# PiBladeBackPlane-V1.net
KiCad netlist of a schematic drawn in EAGLE
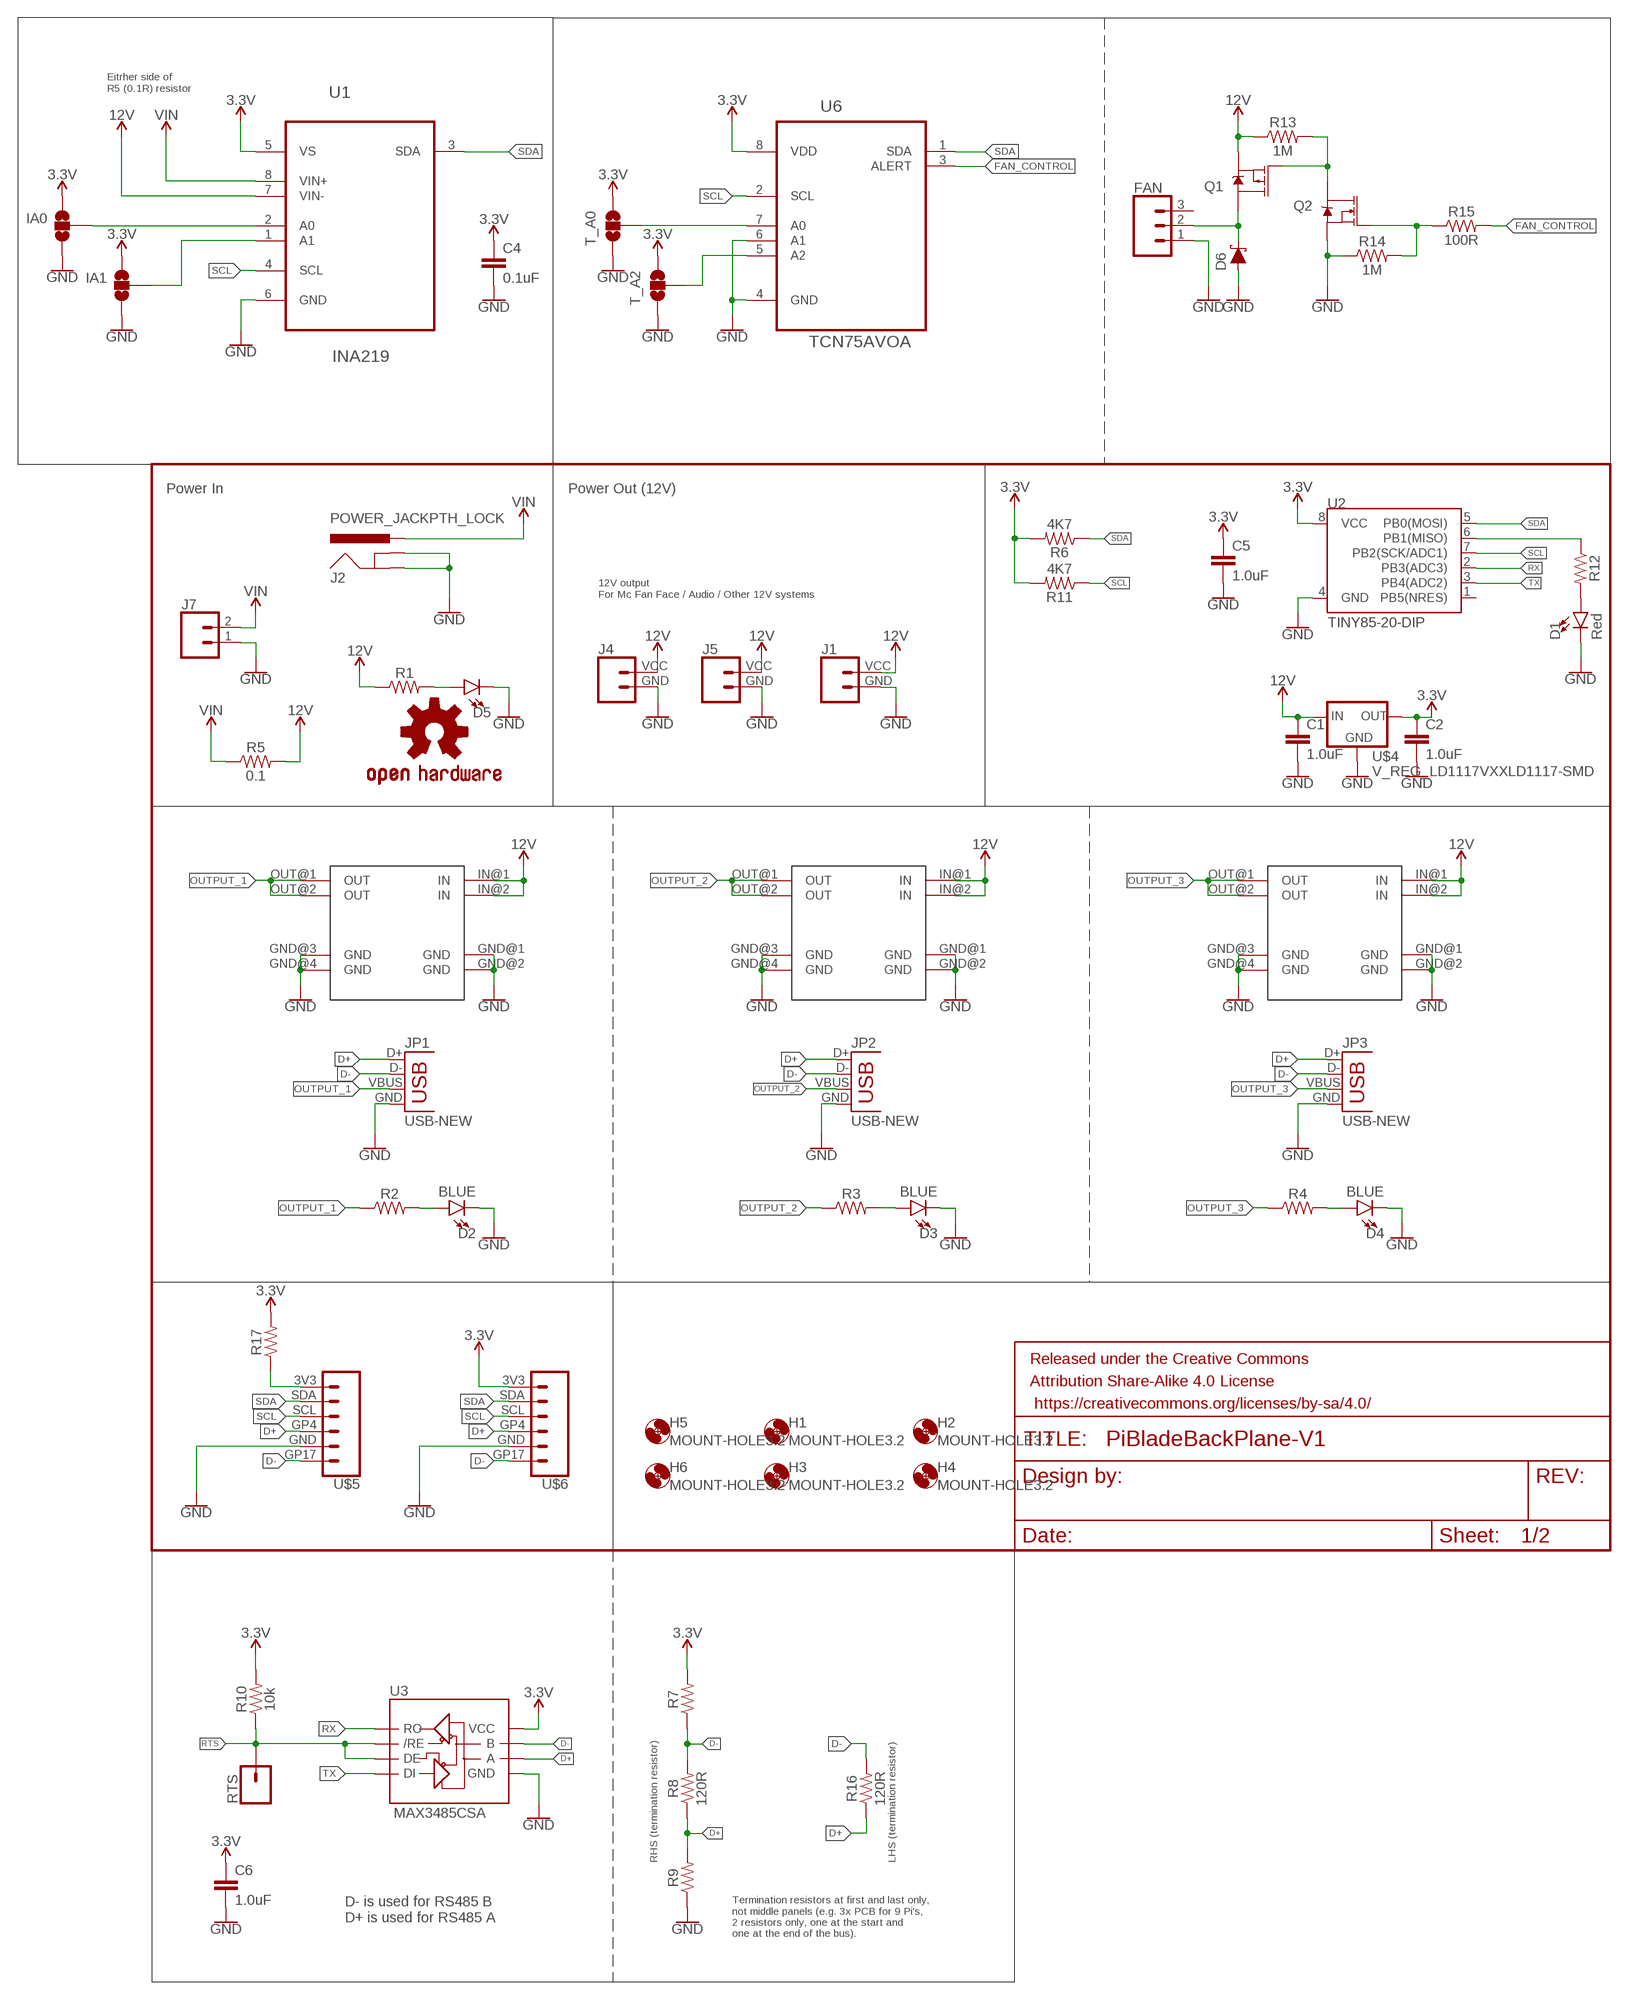
[diagram p0: schematic, sheet 1]

(export (version "E")
  (design (tool "Eeschema 10.0.6"))
  (components
    (comp (ref "C1")
      (value "1.0uF")
      (footprint "eagle-import:0805")
      (libsource (lib "eagle-import") (part "1.0UF-0805-25V-(+80/-20%)"))
    )
    (comp (ref "C2")
      (value "1.0uF")
      (footprint "eagle-import:0805")
      (libsource (lib "eagle-import") (part "1.0UF-0805-25V-(+80/-20%)"))
    )
    (comp (ref "C4")
      (value "0.1uF")
      (footprint "eagle-import:0805")
      (libsource (lib "eagle-import") (part "1.0UF-0805-25V-(+80/-20%)"))
    )
    (comp (ref "C5")
      (value "1.0uF")
      (footprint "eagle-import:0805")
      (libsource (lib "eagle-import") (part "1.0UF-0805-25V-(+80/-20%)"))
    )
    (comp (ref "C6")
      (value "1.0uF")
      (footprint "eagle-import:0805")
      (libsource (lib "eagle-import") (part "1.0UF-0805-25V-(+80/-20%)"))
    )
    (comp (ref "D1")
      (value "Red")
      (footprint "eagle-import:LED-1206")
      (libsource (lib "eagle-import") (part "LED-BLUE1206"))
    )
    (comp (ref "D2")
      (value "BLUE")
      (footprint "eagle-import:LED-1206")
      (libsource (lib "eagle-import") (part "LED-BLUE1206"))
    )
    (comp (ref "D3")
      (value "BLUE")
      (footprint "eagle-import:LED-1206")
      (libsource (lib "eagle-import") (part "LED-BLUE1206"))
    )
    (comp (ref "D4")
      (value "BLUE")
      (footprint "eagle-import:LED-1206")
      (libsource (lib "eagle-import") (part "LED-BLUE1206"))
    )
    (comp (ref "D5")
      (value "LED1206-BOTTOM")
      (footprint "eagle-import:LED-1206-BOTTOM")
      (libsource (lib "eagle-import") (part "LED1206-BOTTOM"))
    )
    (comp (ref "D6")
      (value "1A/23V/620mV")
      (footprint "eagle-import:SOD-323")
      (libsource (lib "eagle-import") (part "DIODE-SCHOTTKY-BAT20J"))
    )
    (comp (ref "FAN")
      (value "CONN_03POLAR")
      (footprint "eagle-import:MOLEX-1X3")
      (libsource (lib "eagle-import") (part "CONN_03POLAR"))
    )
    (comp (ref "FRAME1")
      (value "FRAME-LETTER")
      (footprint "eagle-import:CREATIVE_COMMONS")
      (libsource (lib "eagle-import") (part "FRAME-LETTER"))
    )
    (comp (ref "H1")
      (value "MOUNT-HOLE3.2")
      (footprint "eagle-import:3,2")
      (libsource (lib "eagle-import") (part "MOUNT-HOLE3.2"))
    )
    (comp (ref "H2")
      (value "MOUNT-HOLE3.2")
      (footprint "eagle-import:3,2")
      (libsource (lib "eagle-import") (part "MOUNT-HOLE3.2"))
    )
    (comp (ref "H3")
      (value "MOUNT-HOLE3.2")
      (footprint "eagle-import:3,2")
      (libsource (lib "eagle-import") (part "MOUNT-HOLE3.2"))
    )
    (comp (ref "H4")
      (value "MOUNT-HOLE3.2")
      (footprint "eagle-import:3,2")
      (libsource (lib "eagle-import") (part "MOUNT-HOLE3.2"))
    )
    (comp (ref "H5")
      (value "MOUNT-HOLE3.2")
      (footprint "eagle-import:3,2")
      (libsource (lib "eagle-import") (part "MOUNT-HOLE3.2"))
    )
    (comp (ref "H6")
      (value "MOUNT-HOLE3.2")
      (footprint "eagle-import:3,2")
      (libsource (lib "eagle-import") (part "MOUNT-HOLE3.2"))
    )
    (comp (ref "IA0")
      (value "JUMPER-SMT_3_NO_NO_SILK")
      (footprint "eagle-import:SMT-JUMPER_3_0-NO_TRACE_NO-SILK")
      (libsource (lib "eagle-import") (part "JUMPER-SMT_3_NO_NO_SILK"))
    )
    (comp (ref "IA1")
      (value "JUMPER-SMT_3_NO_NO_SILK")
      (footprint "eagle-import:SMT-JUMPER_3_0-NO_TRACE_NO-SILK")
      (libsource (lib "eagle-import") (part "JUMPER-SMT_3_NO_NO_SILK"))
    )
    (comp (ref "J1")
      (value "CONN_02JST-2-PH-VERT")
      (footprint "eagle-import:JST-2-SMD-VERT")
      (libsource (lib "eagle-import") (part "CONN_02JST-2-PH-VERT"))
    )
    (comp (ref "J2")
      (value "POWER_JACKPTH_LOCK")
      (footprint "eagle-import:POWER_JACK_PTH_LOCK")
      (libsource (lib "eagle-import") (part "POWER_JACKPTH_LOCK"))
    )
    (comp (ref "J4")
      (value "CONN_02JST-2-PH-VERT")
      (footprint "eagle-import:JST-2-SMD-VERT")
      (libsource (lib "eagle-import") (part "CONN_02JST-2-PH-VERT"))
    )
    (comp (ref "J5")
      (value "CONN_02JST-2-PH-VERT")
      (footprint "eagle-import:JST-2-SMD-VERT")
      (libsource (lib "eagle-import") (part "CONN_02JST-2-PH-VERT"))
    )
    (comp (ref "J7")
      (value "CONN_025MM")
      (footprint "eagle-import:SCREWTERMINAL-5MM-2")
      (libsource (lib "eagle-import") (part "CONN_025MM"))
    )
    (comp (ref "JP1")
      (value "USB-NEW")
      (footprint "eagle-import:USB-A-VERTICAL")
      (libsource (lib "eagle-import") (part "USB-NEW"))
    )
    (comp (ref "JP2")
      (value "USB-NEW")
      (footprint "eagle-import:USB-A-VERTICAL")
      (libsource (lib "eagle-import") (part "USB-NEW"))
    )
    (comp (ref "JP3")
      (value "USB-NEW")
      (footprint "eagle-import:USB-A-VERTICAL")
      (libsource (lib "eagle-import") (part "USB-NEW"))
    )
    (comp (ref "LOGO1")
      (value "OSHW-LOGOM")
      (footprint "eagle-import:OSHW-LOGO-M")
      (libsource (lib "eagle-import") (part "OSHW-LOGOM"))
    )
    (comp (ref "Q1")
      (value "4.3A/20V/54mΩ")
      (footprint "eagle-import:SOT23-3")
      (libsource (lib "eagle-import") (part "MOSFET_PCH-IRLML2244"))
    )
    (comp (ref "Q2")
      (value "310mA/60V/1.6Ω")
      (footprint "eagle-import:SOT323")
      (libsource (lib "eagle-import") (part "MOSFET-NCH-2N7002PW"))
    )
    (comp (ref "R1")
      (value "RESISTOR0805")
      (footprint "eagle-import:0805")
      (libsource (lib "eagle-import") (part "RESISTOR0805"))
    )
    (comp (ref "R2")
      (value "RESISTOR0805")
      (footprint "eagle-import:0805")
      (libsource (lib "eagle-import") (part "RESISTOR0805"))
    )
    (comp (ref "R3")
      (value "RESISTOR0805")
      (footprint "eagle-import:0805")
      (libsource (lib "eagle-import") (part "RESISTOR0805"))
    )
    (comp (ref "R4")
      (value "RESISTOR0805")
      (footprint "eagle-import:0805")
      (libsource (lib "eagle-import") (part "RESISTOR0805"))
    )
    (comp (ref "R5")
      (value "0.1")
      (footprint "eagle-import:1210")
      (libsource (lib "eagle-import") (part "0.1OHM-1210-1/2W-1%"))
    )
    (comp (ref "R6")
      (value "4K7")
      (footprint "eagle-import:0805")
      (libsource (lib "eagle-import") (part "RESISTOR0805"))
    )
    (comp (ref "R7")
      (value "RESISTOR0805")
      (footprint "eagle-import:0805")
      (libsource (lib "eagle-import") (part "RESISTOR0805"))
    )
    (comp (ref "R8")
      (value "120R")
      (footprint "eagle-import:0805")
      (libsource (lib "eagle-import") (part "RESISTOR0805"))
    )
    (comp (ref "R9")
      (value "RESISTOR0805")
      (footprint "eagle-import:0805")
      (libsource (lib "eagle-import") (part "RESISTOR0805"))
    )
    (comp (ref "R10")
      (value "10k")
      (footprint "eagle-import:0805")
      (libsource (lib "eagle-import") (part "RESISTOR0805"))
    )
    (comp (ref "R11")
      (value "4K7")
      (footprint "eagle-import:0805")
      (libsource (lib "eagle-import") (part "RESISTOR0805"))
    )
    (comp (ref "R12")
      (value "RESISTOR0805")
      (footprint "eagle-import:0805")
      (libsource (lib "eagle-import") (part "RESISTOR0805"))
    )
    (comp (ref "R13")
      (value "1M")
      (footprint "eagle-import:0805")
      (libsource (lib "eagle-import") (part "RESISTOR0805"))
    )
    (comp (ref "R14")
      (value "1M")
      (footprint "eagle-import:0805")
      (libsource (lib "eagle-import") (part "RESISTOR0805"))
    )
    (comp (ref "R15")
      (value "100R")
      (footprint "eagle-import:0805")
      (libsource (lib "eagle-import") (part "RESISTOR0805"))
    )
    (comp (ref "R16")
      (value "120R")
      (footprint "eagle-import:0805")
      (libsource (lib "eagle-import") (part "RESISTOR0805"))
    )
    (comp (ref "R17")
      (value "RESISTOR1206")
      (footprint "eagle-import:1206")
      (libsource (lib "eagle-import") (part "RESISTOR1206"))
    )
    (comp (ref "RTS")
      (value "CONN_01")
      (footprint "eagle-import:1X01")
      (libsource (lib "eagle-import") (part "CONN_01"))
    )
    (comp (ref "T_A0")
      (value "JUMPER-SMT_3_NO_NO_SILK")
      (footprint "eagle-import:SMT-JUMPER_3_0-NO_TRACE_NO-SILK")
      (libsource (lib "eagle-import") (part "JUMPER-SMT_3_NO_NO_SILK"))
    )
    (comp (ref "T_A2")
      (value "JUMPER-SMT_3_NO_NO_SILK")
      (footprint "eagle-import:SMT-JUMPER_3_0-NO_TRACE_NO-SILK")
      (libsource (lib "eagle-import") (part "JUMPER-SMT_3_NO_NO_SILK"))
    )
    (comp (ref "U$1")
      (value "MINI-BUCK-MODULE-3A")
      (footprint "eagle-import:MINI-BUCK-MODULE-3A")
      (libsource (lib "eagle-import") (part "MINI-BUCK-MODULE-3A"))
    )
    (comp (ref "U$2")
      (value "MINI-BUCK-MODULE-3A")
      (footprint "eagle-import:MINI-BUCK-MODULE-3A")
      (libsource (lib "eagle-import") (part "MINI-BUCK-MODULE-3A"))
    )
    (comp (ref "U$3")
      (value "MINI-BUCK-MODULE-3A")
      (footprint "eagle-import:MINI-BUCK-MODULE-3A")
      (libsource (lib "eagle-import") (part "MINI-BUCK-MODULE-3A"))
    )
    (comp (ref "U$4")
      (value "V_REG_LD1117VXXLD1117-SMD")
      (footprint "eagle-import:SOT223")
      (libsource (lib "eagle-import") (part "V_REG_LD1117VXXLD1117-SMD"))
    )
    (comp (ref "U$5")
      (value "MC_PI_FACE_CONNECTORS_I2CTOP")
      (footprint "eagle-import:JST-6-SH-1.0MM-TOP")
      (libsource (lib "eagle-import") (part "MC_PI_FACE_CONNECTORS_I2CTOP"))
    )
    (comp (ref "U$6")
      (value "MC_PI_FACE_CONNECTORS_I2CTOP")
      (footprint "eagle-import:JST-6-SH-1.0MM-TOP")
      (libsource (lib "eagle-import") (part "MC_PI_FACE_CONNECTORS_I2CTOP"))
    )
    (comp (ref "U1")
      (value "INA219")
      (footprint "eagle-import:SO08")
      (libsource (lib "eagle-import") (part "INA219AIDCNRSOIC"))
    )
    (comp (ref "U2")
      (value "TINY85-20-DIP")
      (footprint "eagle-import:DIP08_MCU")
      (libsource (lib "eagle-import") (part "ATTINY45TINY85-20-DIP"))
    )
    (comp (ref "U3")
      (value "MAX3485CSA")
      (footprint "eagle-import:SO08")
      (libsource (lib "eagle-import") (part "RS485SOIC"))
    )
    (comp (ref "U6")
      (value "TCN75AVOA")
      (footprint "eagle-import:SOIC127P600X175-8N")
      (fields (field (name "MPN") "TCN75AVOA "))
      (libsource (lib "eagle-import") (part "TCN75AVOA"))
    )
  )
  (nets
    (net (code "1") (name "3.3V") (class "Default")
      (node (ref "C2") (pin "1") (pinfunction "1_1") (pintype "passive"))
      (node (ref "C4") (pin "1") (pinfunction "1_1") (pintype "passive"))
      (node (ref "C5") (pin "1") (pinfunction "1_1") (pintype "passive"))
      (node (ref "C6") (pin "1") (pinfunction "1_1") (pintype "passive"))
      (node (ref "IA0") (pin "1") (pinfunction "1_1") (pintype "passive"))
      (node (ref "IA1") (pin "1") (pinfunction "1_1") (pintype "passive"))
      (node (ref "R10") (pin "2") (pinfunction "2_2") (pintype "passive"))
      (node (ref "R11") (pin "2") (pinfunction "2_2") (pintype "passive"))
      (node (ref "R17") (pin "2") (pinfunction "2_2") (pintype "passive"))
      (node (ref "R6") (pin "2") (pinfunction "2_2") (pintype "passive"))
      (node (ref "R7") (pin "2") (pinfunction "2_2") (pintype "passive"))
      (node (ref "T_A0") (pin "1") (pinfunction "1_1") (pintype "passive"))
      (node (ref "T_A2") (pin "1") (pinfunction "1_1") (pintype "passive"))
      (node (ref "U$4") (pin "2") (pinfunction "OUT_2") (pintype "passive"))
      (node (ref "U$6") (pin "3V3") (pinfunction "3V3_3V3") (pintype "power_in"))
      (node (ref "U1") (pin "5") (pinfunction "VS_5") (pintype "power_in"))
      (node (ref "U2") (pin "8") (pinfunction "VCC_8") (pintype "bidirectional"))
      (node (ref "U3") (pin "8") (pinfunction "VCC_8") (pintype "bidirectional"))
      (node (ref "U6") (pin "8") (pinfunction "VDD_8") (pintype "power_in"))
    )
    (net (code "2") (name "12V") (class "Default")
      (node (ref "C1") (pin "1") (pinfunction "1_1") (pintype "passive"))
      (node (ref "J1") (pin "VCC") (pinfunction "2_VCC") (pintype "passive"))
      (node (ref "J4") (pin "VCC") (pinfunction "2_VCC") (pintype "passive"))
      (node (ref "J5") (pin "VCC") (pinfunction "2_VCC") (pintype "passive"))
      (node (ref "Q1") (pin "2") (pinfunction "S_2") (pintype "bidirectional"))
      (node (ref "R1") (pin "1") (pinfunction "1_1") (pintype "passive"))
      (node (ref "R13") (pin "1") (pinfunction "1_1") (pintype "passive"))
      (node (ref "R5") (pin "2") (pinfunction "2_2") (pintype "passive"))
      (node (ref "U$1") (pin "IN@1") (pinfunction "IN_IN@1") (pintype "bidirectional"))
      (node (ref "U$1") (pin "IN@2") (pinfunction "IN_IN@2") (pintype "bidirectional"))
      (node (ref "U$2") (pin "IN@1") (pinfunction "IN_IN@1") (pintype "bidirectional"))
      (node (ref "U$2") (pin "IN@2") (pinfunction "IN_IN@2") (pintype "bidirectional"))
      (node (ref "U$3") (pin "IN@1") (pinfunction "IN_IN@1") (pintype "bidirectional"))
      (node (ref "U$3") (pin "IN@2") (pinfunction "IN_IN@2") (pintype "bidirectional"))
      (node (ref "U$4") (pin "3") (pinfunction "IN_3") (pintype "input"))
      (node (ref "U1") (pin "7") (pinfunction "VIN-_7") (pintype "input"))
    )
    (net (code "3") (name "D+") (class "Default")
      (node (ref "JP1") (pin "D+") (pinfunction "D+_D+") (pintype "bidirectional"))
      (node (ref "JP2") (pin "D+") (pinfunction "D+_D+") (pintype "bidirectional"))
      (node (ref "JP3") (pin "D+") (pinfunction "D+_D+") (pintype "bidirectional"))
      (node (ref "R16") (pin "1") (pinfunction "1_1") (pintype "passive"))
      (node (ref "R8") (pin "1") (pinfunction "1_1") (pintype "passive"))
      (node (ref "R9") (pin "2") (pinfunction "2_2") (pintype "passive"))
      (node (ref "U$5") (pin "GP4") (pinfunction "GP4_GP4") (pintype "bidirectional"))
      (node (ref "U$6") (pin "GP4") (pinfunction "GP4_GP4") (pintype "bidirectional"))
      (node (ref "U3") (pin "6") (pinfunction "A_6") (pintype "bidirectional"))
    )
    (net (code "4") (name "D-") (class "Default")
      (node (ref "JP1") (pin "D-") (pinfunction "D-_D-") (pintype "bidirectional"))
      (node (ref "JP2") (pin "D-") (pinfunction "D-_D-") (pintype "bidirectional"))
      (node (ref "JP3") (pin "D-") (pinfunction "D-_D-") (pintype "bidirectional"))
      (node (ref "R16") (pin "2") (pinfunction "2_2") (pintype "passive"))
      (node (ref "R7") (pin "1") (pinfunction "1_1") (pintype "passive"))
      (node (ref "R8") (pin "2") (pinfunction "2_2") (pintype "passive"))
      (node (ref "U$5") (pin "GP17") (pinfunction "GP17_GP17") (pintype "bidirectional"))
      (node (ref "U$6") (pin "GP17") (pinfunction "GP17_GP17") (pintype "bidirectional"))
      (node (ref "U3") (pin "7") (pinfunction "B_7") (pintype "bidirectional"))
    )
    (net (code "5") (name "FAN_CONTROL") (class "Default")
      (node (ref "R15") (pin "2") (pinfunction "2_2") (pintype "passive"))
      (node (ref "U6") (pin "3") (pinfunction "ALERT_3") (pintype "output"))
    )
    (net (code "6") (name "GND") (class "Default")
      (node (ref "C1") (pin "2") (pinfunction "2_2") (pintype "passive"))
      (node (ref "C2") (pin "2") (pinfunction "2_2") (pintype "passive"))
      (node (ref "C4") (pin "2") (pinfunction "2_2") (pintype "passive"))
      (node (ref "C5") (pin "2") (pinfunction "2_2") (pintype "passive"))
      (node (ref "C6") (pin "2") (pinfunction "2_2") (pintype "passive"))
      (node (ref "D1") (pin "C") (pinfunction "C_C") (pintype "passive"))
      (node (ref "D2") (pin "C") (pinfunction "C_C") (pintype "passive"))
      (node (ref "D3") (pin "C") (pinfunction "C_C") (pintype "passive"))
      (node (ref "D4") (pin "C") (pinfunction "C_C") (pintype "passive"))
      (node (ref "D5") (pin "C") (pinfunction "C_C") (pintype "passive"))
      (node (ref "D6") (pin "A") (pinfunction "A_A") (pintype "passive"))
      (node (ref "FAN") (pin "1") (pinfunction "1_1") (pintype "passive"))
      (node (ref "IA0") (pin "3") (pinfunction "3_3") (pintype "passive"))
      (node (ref "IA1") (pin "3") (pinfunction "3_3") (pintype "passive"))
      (node (ref "J1") (pin "GND") (pinfunction "1_GND") (pintype "passive"))
      (node (ref "J2") (pin "GND") (pinfunction "GND_GND") (pintype "bidirectional"))
      (node (ref "J2") (pin "GNDBREAK") (pinfunction "GNDBREAK_GNDBREAK") (pintype "bidirectional"))
      (node (ref "J4") (pin "GND") (pinfunction "1_GND") (pintype "passive"))
      (node (ref "J5") (pin "GND") (pinfunction "1_GND") (pintype "passive"))
      (node (ref "J7") (pin "1") (pinfunction "1_1") (pintype "passive"))
      (node (ref "JP1") (pin "GND") (pinfunction "GND_GND") (pintype "bidirectional"))
      (node (ref "JP2") (pin "GND") (pinfunction "GND_GND") (pintype "bidirectional"))
      (node (ref "JP3") (pin "GND") (pinfunction "GND_GND") (pintype "bidirectional"))
      (node (ref "Q2") (pin "2") (pinfunction "S_2") (pintype "bidirectional"))
      (node (ref "R14") (pin "1") (pinfunction "1_1") (pintype "passive"))
      (node (ref "R9") (pin "1") (pinfunction "1_1") (pintype "passive"))
      (node (ref "T_A0") (pin "3") (pinfunction "3_3") (pintype "passive"))
      (node (ref "T_A2") (pin "3") (pinfunction "3_3") (pintype "passive"))
      (node (ref "U$1") (pin "GND@1") (pinfunction "GND_GND@1") (pintype "bidirectional"))
      (node (ref "U$1") (pin "GND@2") (pinfunction "GND_GND@2") (pintype "bidirectional"))
      (node (ref "U$1") (pin "GND@3") (pinfunction "GND_GND@3") (pintype "bidirectional"))
      (node (ref "U$1") (pin "GND@4") (pinfunction "GND_GND@4") (pintype "bidirectional"))
      (node (ref "U$2") (pin "GND@1") (pinfunction "GND_GND@1") (pintype "bidirectional"))
      (node (ref "U$2") (pin "GND@2") (pinfunction "GND_GND@2") (pintype "bidirectional"))
      (node (ref "U$2") (pin "GND@3") (pinfunction "GND_GND@3") (pintype "bidirectional"))
      (node (ref "U$2") (pin "GND@4") (pinfunction "GND_GND@4") (pintype "bidirectional"))
      (node (ref "U$3") (pin "GND@1") (pinfunction "GND_GND@1") (pintype "bidirectional"))
      (node (ref "U$3") (pin "GND@2") (pinfunction "GND_GND@2") (pintype "bidirectional"))
      (node (ref "U$3") (pin "GND@3") (pinfunction "GND_GND@3") (pintype "bidirectional"))
      (node (ref "U$3") (pin "GND@4") (pinfunction "GND_GND@4") (pintype "bidirectional"))
      (node (ref "U$4") (pin "1") (pinfunction "GND_1") (pintype "input"))
      (node (ref "U$5") (pin "GND") (pinfunction "GND_GND") (pintype "power_in"))
      (node (ref "U$6") (pin "GND") (pinfunction "GND_GND") (pintype "power_in"))
      (node (ref "U1") (pin "6") (pinfunction "GND_6") (pintype "passive"))
      (node (ref "U2") (pin "4") (pinfunction "GND_4") (pintype "bidirectional"))
      (node (ref "U3") (pin "5") (pinfunction "GND_5") (pintype "bidirectional"))
      (node (ref "U6") (pin "4") (pinfunction "GND_4") (pintype "power_in"))
      (node (ref "U6") (pin "6") (pinfunction "A1_6") (pintype "input"))
    )
    (net (code "7") (name "Net-(D1-PadA)") (class "Default")
      (node (ref "D1") (pin "A") (pinfunction "A_A") (pintype "passive"))
      (node (ref "R12") (pin "2") (pinfunction "2_2") (pintype "passive"))
    )
    (net (code "8") (name "Net-(D2-PadA)") (class "Default")
      (node (ref "D2") (pin "A") (pinfunction "A_A") (pintype "passive"))
      (node (ref "R2") (pin "2") (pinfunction "2_2") (pintype "passive"))
    )
    (net (code "9") (name "Net-(D3-PadA)") (class "Default")
      (node (ref "D3") (pin "A") (pinfunction "A_A") (pintype "passive"))
      (node (ref "R3") (pin "2") (pinfunction "2_2") (pintype "passive"))
    )
    (net (code "10") (name "Net-(D4-PadA)") (class "Default")
      (node (ref "D4") (pin "A") (pinfunction "A_A") (pintype "passive"))
      (node (ref "R4") (pin "2") (pinfunction "2_2") (pintype "passive"))
    )
    (net (code "11") (name "Net-(D5-PadA)") (class "Default")
      (node (ref "D5") (pin "A") (pinfunction "A_A") (pintype "passive"))
      (node (ref "R1") (pin "2") (pinfunction "2_2") (pintype "passive"))
    )
    (net (code "12") (name "Net-(Q1-D)") (class "Default")
      (node (ref "D6") (pin "C") (pinfunction "C_C") (pintype "passive"))
      (node (ref "FAN") (pin "2") (pinfunction "2_2") (pintype "passive"))
      (node (ref "Q1") (pin "3") (pinfunction "D_3") (pintype "bidirectional"))
    )
    (net (code "13") (name "Net-(Q1-G)") (class "Default")
      (node (ref "Q1") (pin "1") (pinfunction "G_1") (pintype "bidirectional"))
      (node (ref "Q2") (pin "3") (pinfunction "D_3") (pintype "bidirectional"))
      (node (ref "R13") (pin "2") (pinfunction "2_2") (pintype "passive"))
    )
    (net (code "14") (name "Net-(Q2-G)") (class "Default")
      (node (ref "Q2") (pin "1") (pinfunction "G_1") (pintype "bidirectional"))
      (node (ref "R14") (pin "2") (pinfunction "2_2") (pintype "passive"))
      (node (ref "R15") (pin "1") (pinfunction "1_1") (pintype "passive"))
    )
    (net (code "15") (name "Net-(R17-Pad1)") (class "Default")
      (node (ref "R17") (pin "1") (pinfunction "1_1") (pintype "passive"))
      (node (ref "U$5") (pin "3V3") (pinfunction "3V3_3V3") (pintype "power_in"))
    )
    (net (code "16") (name "Net-(U1-A0)") (class "Default")
      (node (ref "IA0") (pin "2") (pinfunction "2_2") (pintype "passive"))
      (node (ref "U1") (pin "2") (pinfunction "A0_2") (pintype "input"))
    )
    (net (code "17") (name "Net-(U1-A1)") (class "Default")
      (node (ref "IA1") (pin "2") (pinfunction "2_2") (pintype "passive"))
      (node (ref "U1") (pin "1") (pinfunction "A1_1") (pintype "input"))
    )
    (net (code "18") (name "Net-(U2-PB1(MISO))") (class "Default")
      (node (ref "R12") (pin "1") (pinfunction "1_1") (pintype "passive"))
      (node (ref "U2") (pin "6") (pinfunction "PB1(MISO)_6") (pintype "bidirectional"))
    )
    (net (code "19") (name "Net-(U6-A0)") (class "Default")
      (node (ref "T_A0") (pin "2") (pinfunction "2_2") (pintype "passive"))
      (node (ref "U6") (pin "7") (pinfunction "A0_7") (pintype "input"))
    )
    (net (code "20") (name "Net-(U6-A2)") (class "Default")
      (node (ref "T_A2") (pin "2") (pinfunction "2_2") (pintype "passive"))
      (node (ref "U6") (pin "5") (pinfunction "A2_5") (pintype "input"))
    )
    (net (code "21") (name "OUTPUT_1") (class "Default")
      (node (ref "JP1") (pin "VBUS") (pinfunction "VBUS_VBUS") (pintype "bidirectional"))
      (node (ref "R2") (pin "1") (pinfunction "1_1") (pintype "passive"))
      (node (ref "U$1") (pin "OUT@1") (pinfunction "OUT_OUT@1") (pintype "bidirectional"))
      (node (ref "U$1") (pin "OUT@2") (pinfunction "OUT_OUT@2") (pintype "bidirectional"))
    )
    (net (code "22") (name "OUTPUT_2") (class "Default")
      (node (ref "JP2") (pin "VBUS") (pinfunction "VBUS_VBUS") (pintype "bidirectional"))
      (node (ref "R3") (pin "1") (pinfunction "1_1") (pintype "passive"))
      (node (ref "U$2") (pin "OUT@1") (pinfunction "OUT_OUT@1") (pintype "bidirectional"))
      (node (ref "U$2") (pin "OUT@2") (pinfunction "OUT_OUT@2") (pintype "bidirectional"))
    )
    (net (code "23") (name "OUTPUT_3") (class "Default")
      (node (ref "JP3") (pin "VBUS") (pinfunction "VBUS_VBUS") (pintype "bidirectional"))
      (node (ref "R4") (pin "1") (pinfunction "1_1") (pintype "passive"))
      (node (ref "U$3") (pin "OUT@1") (pinfunction "OUT_OUT@1") (pintype "bidirectional"))
      (node (ref "U$3") (pin "OUT@2") (pinfunction "OUT_OUT@2") (pintype "bidirectional"))
    )
    (net (code "24") (name "RTS") (class "Default")
      (node (ref "R10") (pin "1") (pinfunction "1_1") (pintype "passive"))
      (node (ref "RTS") (pin "1") (pinfunction "1_1") (pintype "passive"))
      (node (ref "U3") (pin "2") (pinfunction "/RE_2") (pintype "bidirectional"))
      (node (ref "U3") (pin "3") (pinfunction "DE_3") (pintype "bidirectional"))
    )
    (net (code "25") (name "RX") (class "Default")
      (node (ref "U2") (pin "2") (pinfunction "PB3(ADC3)_2") (pintype "bidirectional"))
      (node (ref "U3") (pin "1") (pinfunction "RO_1") (pintype "bidirectional"))
    )
    (net (code "26") (name "SCL") (class "Default")
      (node (ref "R11") (pin "1") (pinfunction "1_1") (pintype "passive"))
      (node (ref "U$5") (pin "SCL") (pinfunction "SCL_SCL") (pintype "bidirectional"))
      (node (ref "U$6") (pin "SCL") (pinfunction "SCL_SCL") (pintype "bidirectional"))
      (node (ref "U1") (pin "4") (pinfunction "SCL_4") (pintype "input"))
      (node (ref "U2") (pin "7") (pinfunction "PB2(SCK/ADC1)_7") (pintype "bidirectional"))
      (node (ref "U6") (pin "2") (pinfunction "SCL_2") (pintype "input"))
    )
    (net (code "27") (name "SDA") (class "Default")
      (node (ref "R6") (pin "1") (pinfunction "1_1") (pintype "passive"))
      (node (ref "U$5") (pin "SDA") (pinfunction "SDA_SDA") (pintype "bidirectional"))
      (node (ref "U$6") (pin "SDA") (pinfunction "SDA_SDA") (pintype "bidirectional"))
      (node (ref "U1") (pin "3") (pinfunction "SDA_3") (pintype "bidirectional"))
      (node (ref "U2") (pin "5") (pinfunction "PB0(MOSI)_5") (pintype "bidirectional"))
      (node (ref "U6") (pin "1") (pinfunction "SDA_1") (pintype "bidirectional"))
    )
    (net (code "28") (name "TX") (class "Default")
      (node (ref "U2") (pin "3") (pinfunction "PB4(ADC2)_3") (pintype "bidirectional"))
      (node (ref "U3") (pin "4") (pinfunction "DI_4") (pintype "bidirectional"))
    )
    (net (code "29") (name "VIN") (class "Default")
      (node (ref "J2") (pin "PWR") (pinfunction "PWR_PWR") (pintype "bidirectional"))
      (node (ref "J7") (pin "2") (pinfunction "2_2") (pintype "passive"))
      (node (ref "R5") (pin "1") (pinfunction "1_1") (pintype "passive"))
      (node (ref "U1") (pin "8") (pinfunction "VIN+_8") (pintype "input"))
    )
    (net (code "30") (name "unconnected-(FAN-Pad3)") (class "Default")
      (node (ref "FAN") (pin "3") (pinfunction "3_3") (pintype "passive"))
    )
    (net (code "31") (name "unconnected-(U2-PB5(NRES)-Pad1)") (class "Default")
      (node (ref "U2") (pin "1") (pinfunction "PB5(NRES)_1") (pintype "bidirectional"))
    )
  )
)
